# canbus_shield-v12.net
KiCad netlist of a schematic drawn in EAGLE
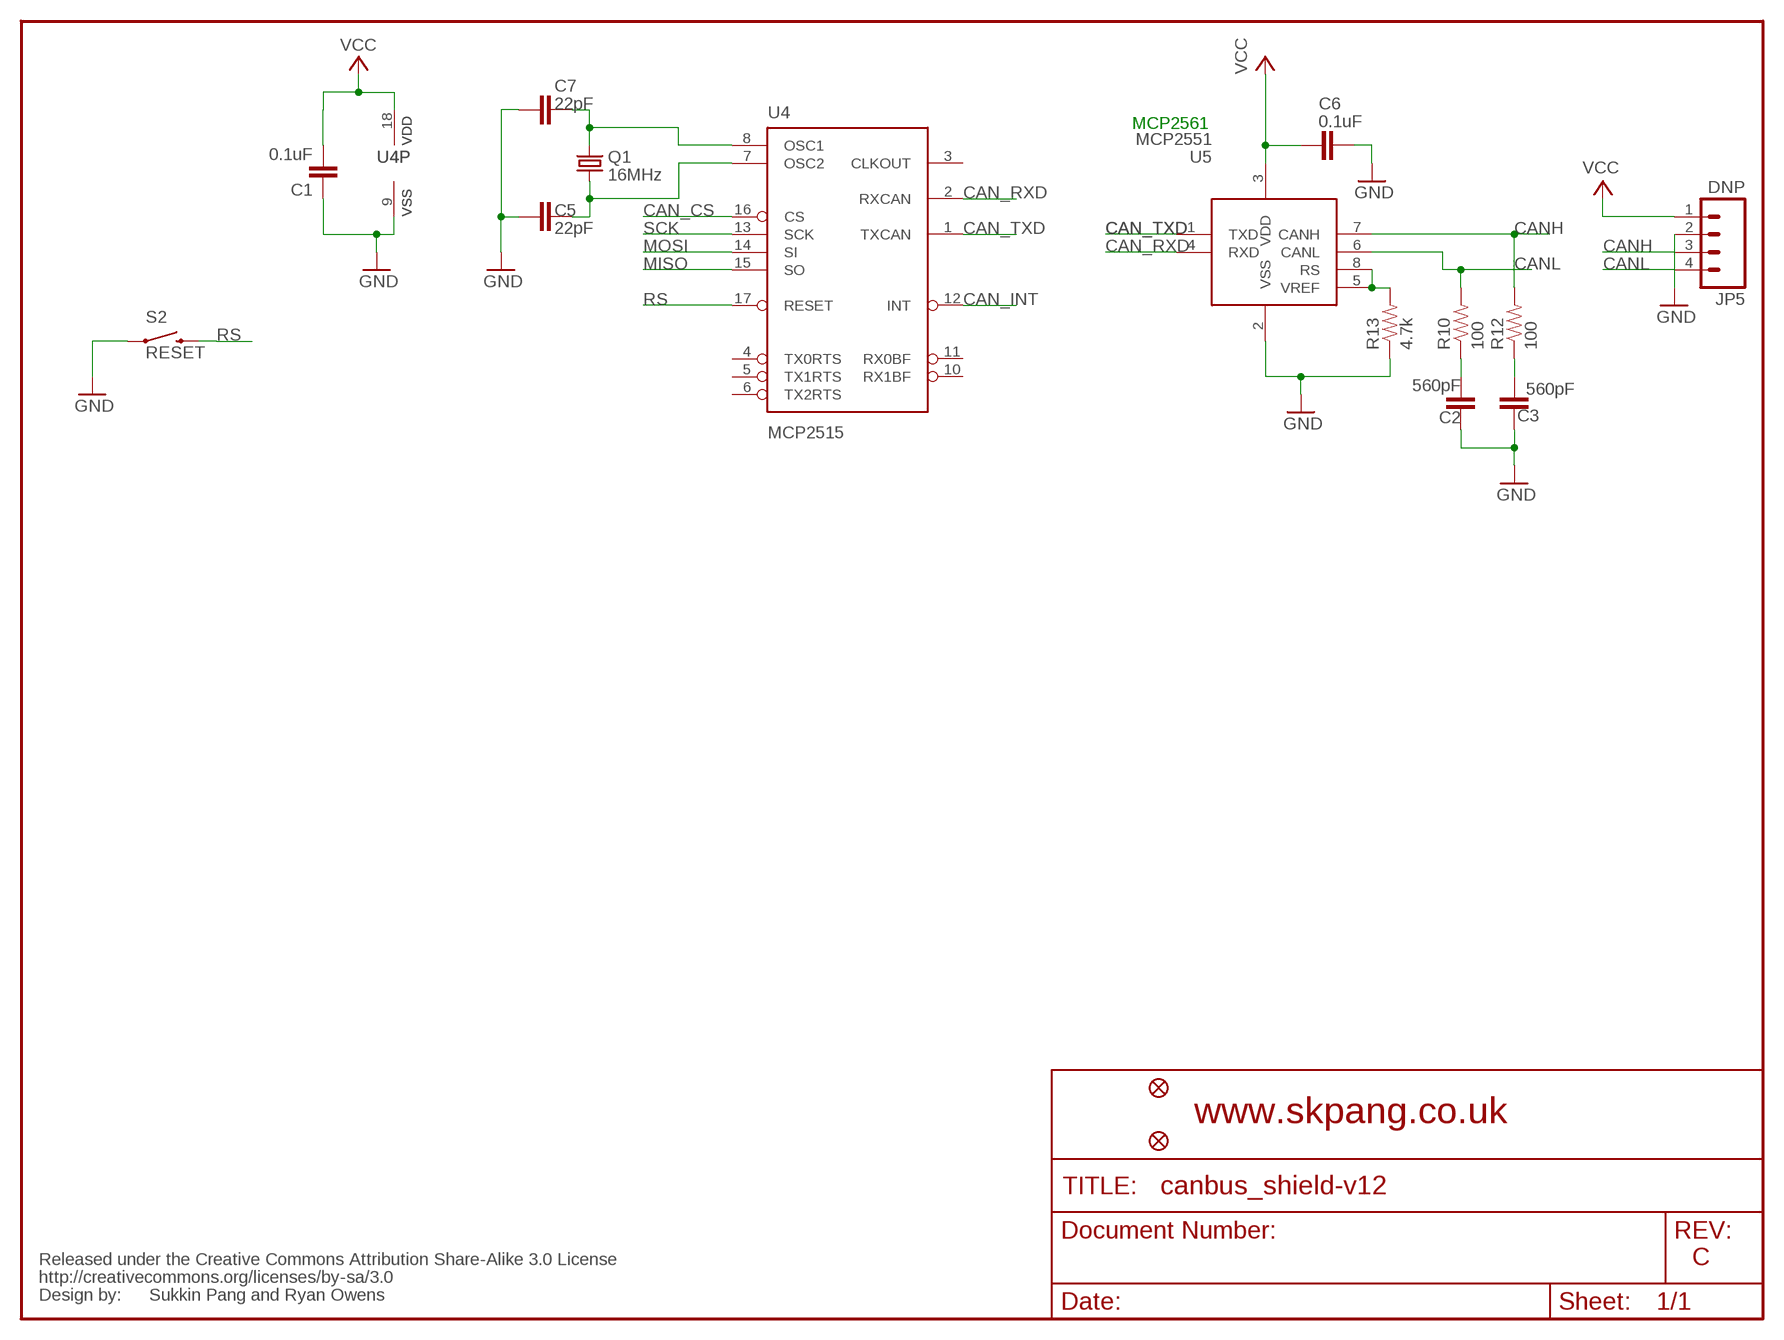
[diagram p0: schematic, sheet 1]

(export (version "E")
  (design (tool "Eeschema 10.0.6"))
  (components
    (comp (ref "C1")
      (value "0.1uF")
      (footprint "eagle-import:0603-CAP")
      (libsource (lib "eagle-import") (part "CAP0603-CAP"))
    )
    (comp (ref "C2")
      (value "560pF")
      (footprint "eagle-import:0603-CAP")
      (libsource (lib "eagle-import") (part "CAP0603-CAP"))
    )
    (comp (ref "C3")
      (value "560pF")
      (footprint "eagle-import:0603-CAP")
      (libsource (lib "eagle-import") (part "CAP0603-CAP"))
    )
    (comp (ref "C5")
      (value "22pF")
      (footprint "eagle-import:0603-CAP")
      (libsource (lib "eagle-import") (part "CAP0603-CAP"))
    )
    (comp (ref "C6")
      (value "0.1uF")
      (footprint "eagle-import:0603-CAP")
      (libsource (lib "eagle-import") (part "CAP0603-CAP"))
    )
    (comp (ref "C7")
      (value "22pF")
      (footprint "eagle-import:0603-CAP")
      (libsource (lib "eagle-import") (part "CAP0603-CAP"))
    )
    (comp (ref "JP2")
      (value "FIDUCIAL1X2")
      (footprint "eagle-import:FIDUCIAL-1X2")
      (libsource (lib "eagle-import") (part "FIDUCIAL1X2"))
    )
    (comp (ref "JP3")
      (value "FIDUCIAL1X2")
      (footprint "eagle-import:FIDUCIAL-1X2")
      (libsource (lib "eagle-import") (part "FIDUCIAL1X2"))
    )
    (comp (ref "JP5")
      (value "DNP")
      (footprint "eagle-import:1X04")
      (libsource (lib "eagle-import") (part "M04PTH"))
    )
    (comp (ref "Q1")
      (value "16MHz")
      (footprint "eagle-import:CRYSTAL-SMD-5X3")
      (libsource (lib "eagle-import") (part "CRYSTAL5X3"))
    )
    (comp (ref "R10")
      (value "100")
      (footprint "eagle-import:0603-RES")
      (libsource (lib "eagle-import") (part "RESISTOR0603-RES"))
    )
    (comp (ref "R12")
      (value "100")
      (footprint "eagle-import:0603-RES")
      (libsource (lib "eagle-import") (part "RESISTOR0603-RES"))
    )
    (comp (ref "R13")
      (value "4.7k")
      (footprint "eagle-import:0603-RES")
      (libsource (lib "eagle-import") (part "RESISTOR0603-RES"))
    )
    (comp (ref "S2")
      (value "RESET")
      (footprint "eagle-import:TACTILE_SWITCH_SMD")
      (libsource (lib "eagle-import") (part "SWITCH-MOMENTARY-2SMD"))
    )
    (comp (ref "U$1")
      (value "CREATIVE_COMMONS")
      (footprint "eagle-import:CREATIVE_COMMONS")
      (libsource (lib "eagle-import") (part "CREATIVE_COMMONS"))
    )
    (comp (ref "U4")
      (value "MCP2515")
      (footprint "eagle-import:SO-18W")
      (libsource (lib "eagle-import") (part "MCP2510SO"))
    )
    (comp (ref "U5")
      (value "MCP2551")
      (footprint "eagle-import:SO-08M")
      (libsource (lib "eagle-import") (part "MCP2551"))
    )
  )
  (nets
    (net (code "1") (name "/CANH") (class "Default")
      (node (ref "JP5") (pin "3") (pinfunction "3_3") (pintype "passive"))
      (node (ref "R12") (pin "2") (pinfunction "2_2") (pintype "passive"))
      (node (ref "U5") (pin "7") (pinfunction "CANH_7") (pintype "bidirectional"))
    )
    (net (code "2") (name "/CANL") (class "Default")
      (node (ref "JP5") (pin "4") (pinfunction "4_4") (pintype "passive"))
      (node (ref "R10") (pin "2") (pinfunction "2_2") (pintype "passive"))
      (node (ref "U5") (pin "6") (pinfunction "CANL_6") (pintype "bidirectional"))
    )
    (net (code "3") (name "/CAN_CS") (class "Default")
      (node (ref "U4") (pin "16") (pinfunction "CS_16") (pintype "input"))
    )
    (net (code "4") (name "/CAN_INT") (class "Default")
      (node (ref "U4") (pin "12") (pinfunction "INT_12") (pintype "output"))
    )
    (net (code "5") (name "/CAN_RXD") (class "Default")
      (node (ref "U4") (pin "2") (pinfunction "RXCAN_2") (pintype "input"))
      (node (ref "U5") (pin "4") (pinfunction "RXD_4") (pintype "bidirectional"))
    )
    (net (code "6") (name "/CAN_TXD") (class "Default")
      (node (ref "U4") (pin "1") (pinfunction "TXCAN_1") (pintype "output"))
      (node (ref "U5") (pin "1") (pinfunction "TXD_1") (pintype "bidirectional"))
    )
    (net (code "7") (name "/MISO") (class "Default")
      (node (ref "U4") (pin "15") (pinfunction "SO_15") (pintype "output"))
    )
    (net (code "8") (name "/MOSI") (class "Default")
      (node (ref "U4") (pin "14") (pinfunction "SI_14") (pintype "input"))
    )
    (net (code "9") (name "/RS") (class "Default")
      (node (ref "S2") (pin "3") (pinfunction "2_3") (pintype "passive"))
      (node (ref "U4") (pin "17") (pinfunction "RESET_17") (pintype "input"))
    )
    (net (code "10") (name "/SCK") (class "Default")
      (node (ref "U4") (pin "13") (pinfunction "SCK_13") (pintype "input"))
    )
    (net (code "11") (name "GND") (class "Default")
      (node (ref "C1") (pin "1") (pinfunction "1_1") (pintype "passive"))
      (node (ref "C2") (pin "1") (pinfunction "1_1") (pintype "passive"))
      (node (ref "C3") (pin "1") (pinfunction "1_1") (pintype "passive"))
      (node (ref "C5") (pin "1") (pinfunction "1_1") (pintype "passive"))
      (node (ref "C6") (pin "1") (pinfunction "1_1") (pintype "passive"))
      (node (ref "C7") (pin "1") (pinfunction "1_1") (pintype "passive"))
      (node (ref "JP5") (pin "2") (pinfunction "2_2") (pintype "passive"))
      (node (ref "R13") (pin "1") (pinfunction "1_1") (pintype "passive"))
      (node (ref "S2") (pin "1") (pinfunction "1_1") (pintype "passive"))
      (node (ref "U4") (pin "9") (pinfunction "VSS_9") (pintype "power_in"))
      (node (ref "U5") (pin "2") (pinfunction "VSS_2") (pintype "power_in"))
    )
    (net (code "12") (name "Net-(C2-Pad2)") (class "Default")
      (node (ref "C2") (pin "2") (pinfunction "2_2") (pintype "passive"))
      (node (ref "R10") (pin "1") (pinfunction "1_1") (pintype "passive"))
    )
    (net (code "13") (name "Net-(C3-Pad2)") (class "Default")
      (node (ref "C3") (pin "2") (pinfunction "2_2") (pintype "passive"))
      (node (ref "R12") (pin "1") (pinfunction "1_1") (pintype "passive"))
    )
    (net (code "14") (name "Net-(Q1-2)") (class "Default")
      (node (ref "C7") (pin "2") (pinfunction "2_2") (pintype "passive"))
      (node (ref "Q1") (pin "3") (pinfunction "2_3") (pintype "passive"))
      (node (ref "U4") (pin "8") (pinfunction "OSC1_8") (pintype "input"))
    )
    (net (code "15") (name "Net-(U4A-OSC2)") (class "Default")
      (node (ref "C5") (pin "2") (pinfunction "2_2") (pintype "passive"))
      (node (ref "Q1") (pin "1") (pinfunction "1_1") (pintype "passive"))
      (node (ref "U4") (pin "7") (pinfunction "OSC2_7") (pintype "output"))
    )
    (net (code "16") (name "Net-(U5-RS)") (class "Default")
      (node (ref "R13") (pin "2") (pinfunction "2_2") (pintype "passive"))
      (node (ref "U5") (pin "5") (pinfunction "VREF_5") (pintype "bidirectional"))
      (node (ref "U5") (pin "8") (pinfunction "RS_8") (pintype "bidirectional"))
    )
    (net (code "17") (name "VCC") (class "Default")
      (node (ref "C1") (pin "2") (pinfunction "2_2") (pintype "passive"))
      (node (ref "C6") (pin "2") (pinfunction "2_2") (pintype "passive"))
      (node (ref "JP5") (pin "1") (pinfunction "1_1") (pintype "passive"))
      (node (ref "U4") (pin "18") (pinfunction "VDD_18") (pintype "power_in"))
      (node (ref "U5") (pin "3") (pinfunction "VDD_3") (pintype "power_in"))
    )
    (net (code "18") (name "unconnected-(U4A-CLKOUT-Pad3)") (class "Default")
      (node (ref "U4") (pin "3") (pinfunction "CLKOUT_3") (pintype "output"))
    )
    (net (code "19") (name "unconnected-(U4A-RX0BF-Pad11)") (class "Default")
      (node (ref "U4") (pin "11") (pinfunction "RX0BF_11") (pintype "output"))
    )
    (net (code "20") (name "unconnected-(U4A-RX1BF-Pad10)") (class "Default")
      (node (ref "U4") (pin "10") (pinfunction "RX1BF_10") (pintype "output"))
    )
    (net (code "21") (name "unconnected-(U4A-TX0RTS-Pad4)") (class "Default")
      (node (ref "U4") (pin "4") (pinfunction "TX0RTS_4") (pintype "input"))
    )
    (net (code "22") (name "unconnected-(U4A-TX1RTS-Pad5)") (class "Default")
      (node (ref "U4") (pin "5") (pinfunction "TX1RTS_5") (pintype "input"))
    )
    (net (code "23") (name "unconnected-(U4A-TX2RTS-Pad6)") (class "Default")
      (node (ref "U4") (pin "6") (pinfunction "TX2RTS_6") (pintype "input"))
    )
  )
)
